# rekuperator_THT.net
KiCad netlist of a schematic drawn in EAGLE
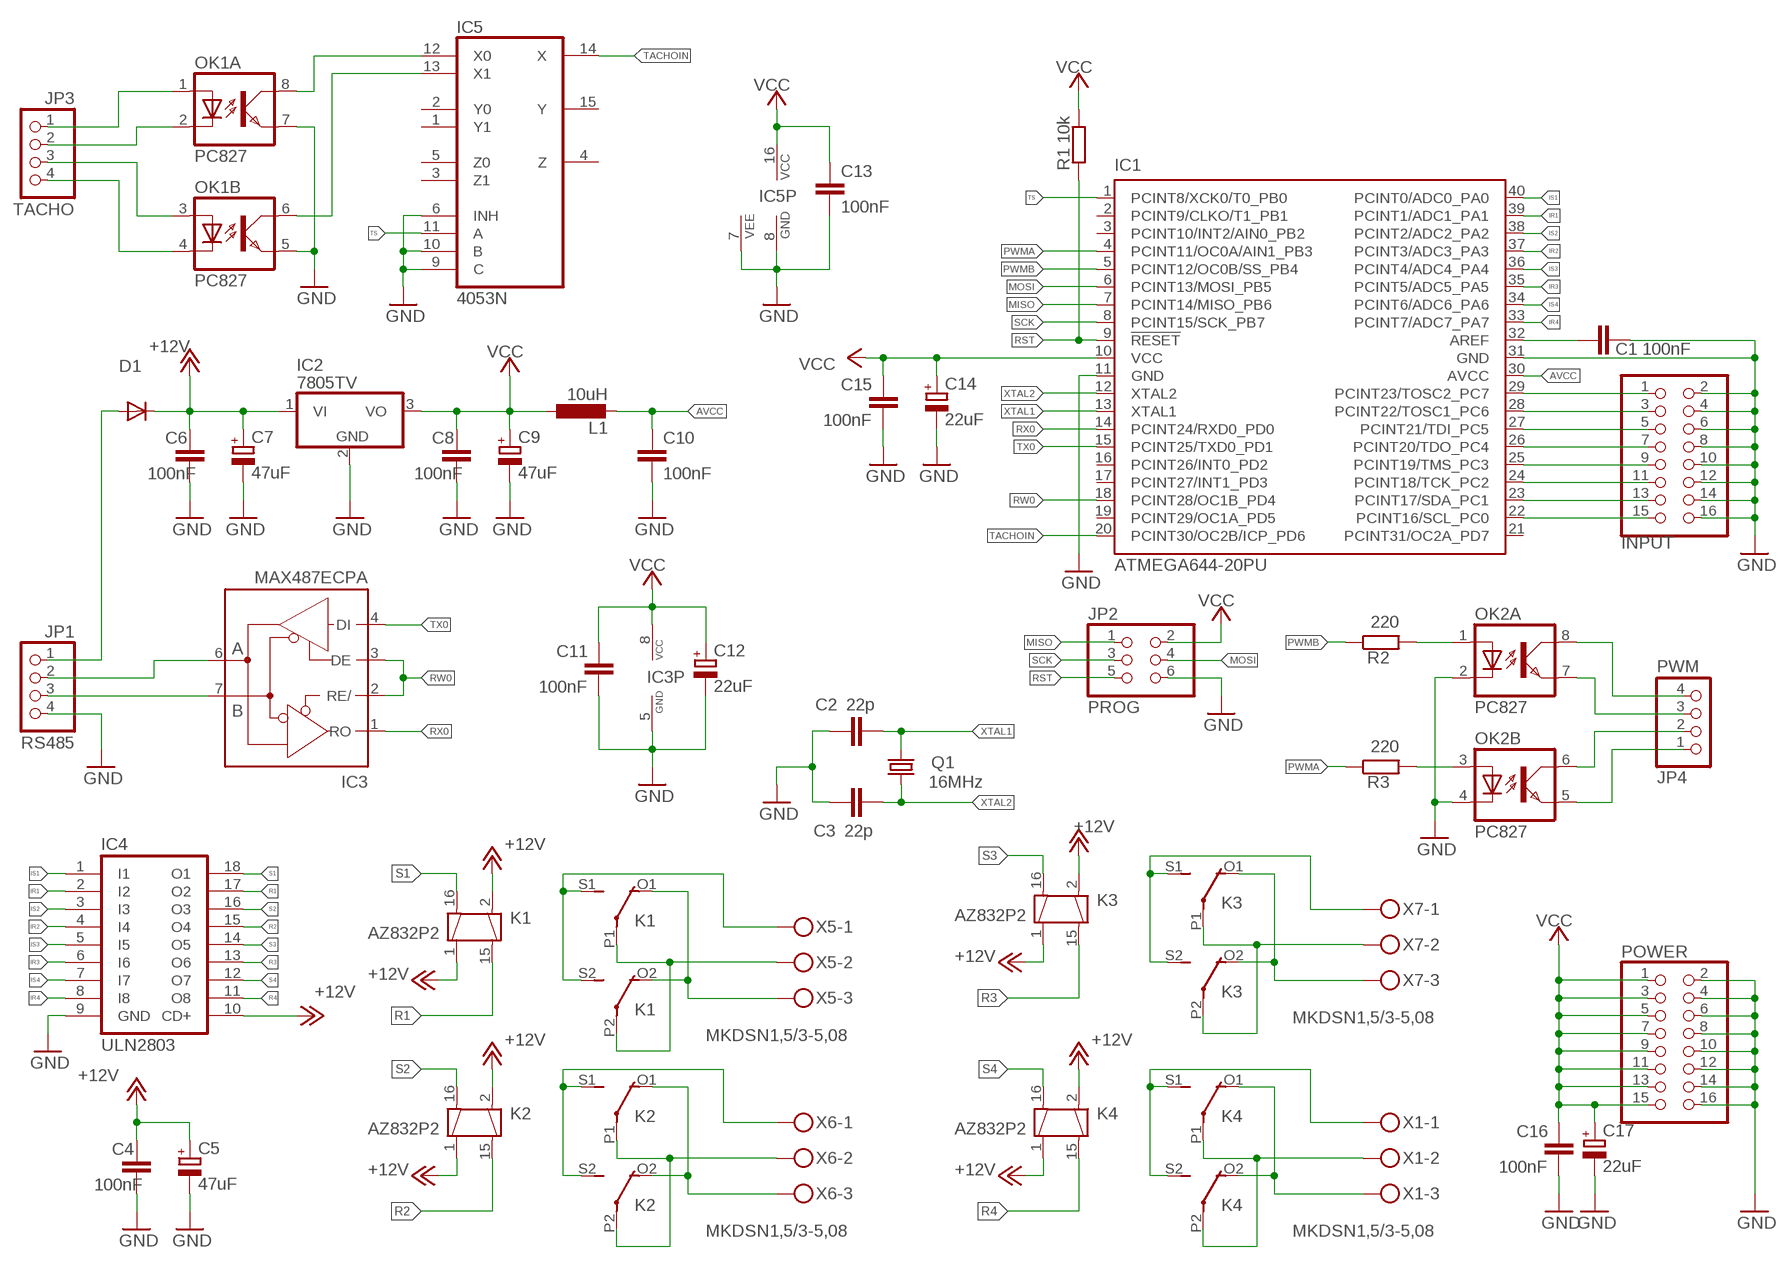
[diagram p0: schematic, sheet 1]

(export (version "E")
  (design (tool "Eeschema 10.0.6"))
  (components
    (comp (ref "C1")
      (value "100nF")
      (footprint "eagle-import:C025-025X050")
      (libsource (lib "eagle-import") (part "C-EU025-025X050"))
    )
    (comp (ref "C2")
      (value "22p")
      (footprint "eagle-import:C025-024X044")
      (libsource (lib "eagle-import") (part "C-EU025-024X044"))
    )
    (comp (ref "C3")
      (value "22p")
      (footprint "eagle-import:C025-024X044")
      (libsource (lib "eagle-import") (part "C-EU025-024X044"))
    )
    (comp (ref "C4")
      (value "100nF")
      (footprint "eagle-import:C025-025X050")
      (libsource (lib "eagle-import") (part "C-EU025-025X050"))
    )
    (comp (ref "C5")
      (value "47uF")
      (footprint "eagle-import:E2,5-6")
      (libsource (lib "eagle-import") (part "CPOL-EUE2.5-6"))
    )
    (comp (ref "C6")
      (value "100nF")
      (footprint "eagle-import:C025-025X050")
      (libsource (lib "eagle-import") (part "C-EU025-025X050"))
    )
    (comp (ref "C7")
      (value "47uF")
      (footprint "eagle-import:E2,5-6")
      (libsource (lib "eagle-import") (part "CPOL-EUE2.5-6"))
    )
    (comp (ref "C8")
      (value "100nF")
      (footprint "eagle-import:C025-025X050")
      (libsource (lib "eagle-import") (part "C-EU025-025X050"))
    )
    (comp (ref "C9")
      (value "47uF")
      (footprint "eagle-import:E2,5-6")
      (libsource (lib "eagle-import") (part "CPOL-EUE2.5-6"))
    )
    (comp (ref "C10")
      (value "100nF")
      (footprint "eagle-import:C025-025X050")
      (libsource (lib "eagle-import") (part "C-EU025-025X050"))
    )
    (comp (ref "C11")
      (value "100nF")
      (footprint "eagle-import:C025-025X050")
      (libsource (lib "eagle-import") (part "C-EU025-025X050"))
    )
    (comp (ref "C12")
      (value "22uF")
      (footprint "eagle-import:E2-5")
      (libsource (lib "eagle-import") (part "CPOL-EUE2-5"))
    )
    (comp (ref "C13")
      (value "100nF")
      (footprint "eagle-import:C025-025X050")
      (libsource (lib "eagle-import") (part "C-EU025-025X050"))
    )
    (comp (ref "C14")
      (value "22uF")
      (footprint "eagle-import:E2-5")
      (libsource (lib "eagle-import") (part "CPOL-EUE2-5"))
    )
    (comp (ref "C15")
      (value "100nF")
      (footprint "eagle-import:C025-025X050")
      (libsource (lib "eagle-import") (part "C-EU025-025X050"))
    )
    (comp (ref "C16")
      (value "100nF")
      (footprint "eagle-import:C025-025X050")
      (libsource (lib "eagle-import") (part "C-EU025-025X050"))
    )
    (comp (ref "C17")
      (value "22uF")
      (footprint "eagle-import:E2-5")
      (libsource (lib "eagle-import") (part "CPOL-EUE2-5"))
    )
    (comp (ref "D1")
      (value "1N4002")
      (footprint "eagle-import:DO34-7")
      (libsource (lib "eagle-import") (part "BAS15"))
    )
    (comp (ref "IC1")
      (value "ATMEGA644-20PU")
      (footprint "eagle-import:DIL40")
      (libsource (lib "eagle-import") (part "ATMEGA644-PU20"))
    )
    (comp (ref "IC2")
      (value "7805TV")
      (footprint "eagle-import:TO220V")
      (libsource (lib "eagle-import") (part "78TV05"))
    )
    (comp (ref "IC3")
      (value "MAX487ECPA")
      (footprint "eagle-import:DIL08")
      (fields (field (name "MPN") "MAX481CPA+"))
      (libsource (lib "eagle-import") (part "MAX481CPA"))
    )
    (comp (ref "IC4")
      (value "ULN2803")
      (footprint "eagle-import:DIL18")
      (libsource (lib "eagle-import") (part "ULN2803A"))
    )
    (comp (ref "IC5")
      (value "4053N")
      (footprint "eagle-import:DIL16")
      (libsource (lib "eagle-import") (part "4053N"))
    )
    (comp (ref "INPUT")
      (value "PINHD-2X8")
      (footprint "eagle-import:2X08")
      (libsource (lib "eagle-import") (part "PINHD-2X8"))
    )
    (comp (ref "JP1")
      (value "RS485")
      (footprint "eagle-import:1X04")
      (libsource (lib "eagle-import") (part "PINHD-1X4"))
    )
    (comp (ref "JP2")
      (value "PROG")
      (footprint "eagle-import:2X03")
      (libsource (lib "eagle-import") (part "PINHD-2X3"))
    )
    (comp (ref "JP3")
      (value "TACHO")
      (footprint "eagle-import:1X04")
      (libsource (lib "eagle-import") (part "PINHD-1X4"))
    )
    (comp (ref "JP4")
      (value "PWM")
      (footprint "eagle-import:1X04")
      (libsource (lib "eagle-import") (part "PINHD-1X4"))
    )
    (comp (ref "K1")
      (value "AZ832P2")
      (footprint "eagle-import:DS2E-L2")
      (libsource (lib "eagle-import") (part "DS2-L2-24V"))
    )
    (comp (ref "K2")
      (value "AZ832P2")
      (footprint "eagle-import:DS2E-L2")
      (libsource (lib "eagle-import") (part "DS2-L2-24V"))
    )
    (comp (ref "K3")
      (value "AZ832P2")
      (footprint "eagle-import:DS2E-L2")
      (libsource (lib "eagle-import") (part "DS2-L2-24V"))
    )
    (comp (ref "K4")
      (value "AZ832P2")
      (footprint "eagle-import:DS2E-L2")
      (libsource (lib "eagle-import") (part "DS2-L2-24V"))
    )
    (comp (ref "L1")
      (value "10uH")
      (footprint "eagle-import:0207_12")
      (libsource (lib "eagle-import") (part "L-EU0207/12"))
    )
    (comp (ref "OK1")
      (value "PC827")
      (footprint "eagle-import:DIL08")
      (libsource (lib "eagle-import") (part "PC827"))
    )
    (comp (ref "OK2")
      (value "PC827")
      (footprint "eagle-import:DIL08")
      (libsource (lib "eagle-import") (part "PC827"))
    )
    (comp (ref "POWER")
      (value "PINHD-2X8")
      (footprint "eagle-import:2X08")
      (libsource (lib "eagle-import") (part "PINHD-2X8"))
    )
    (comp (ref "Q1")
      (value "16MHz")
      (footprint "eagle-import:HC49_S")
      (libsource (lib "eagle-import") (part "CRYSTALHC49S"))
    )
    (comp (ref "R1")
      (value "10k")
      (footprint "eagle-import:0204V")
      (libsource (lib "eagle-import") (part "R-EU_0204/2V"))
    )
    (comp (ref "R2")
      (value "220")
      (footprint "eagle-import:0207_12")
      (libsource (lib "eagle-import") (part "R-EU_0207/12"))
    )
    (comp (ref "R3")
      (value "220")
      (footprint "eagle-import:0207_12")
      (libsource (lib "eagle-import") (part "R-EU_0207/12"))
    )
    (comp (ref "X1")
      (value "MKDSN1,5/3-5,08")
      (footprint "eagle-import:MKDSN1,5_3-5,08")
      (fields (field (name "MPN") "SMKDSN1,5/3-5,08"))
      (libsource (lib "eagle-import") (part "MKDSN1,5/3-5,08"))
    )
    (comp (ref "X5")
      (value "MKDSN1,5/3-5,08")
      (footprint "eagle-import:MKDSN1,5_3-5,08")
      (fields (field (name "MPN") "SMKDSN1,5/3-5,08"))
      (libsource (lib "eagle-import") (part "MKDSN1,5/3-5,08"))
    )
    (comp (ref "X6")
      (value "MKDSN1,5/3-5,08")
      (footprint "eagle-import:MKDSN1,5_3-5,08")
      (fields (field (name "MPN") "SMKDSN1,5/3-5,08"))
      (libsource (lib "eagle-import") (part "MKDSN1,5/3-5,08"))
    )
    (comp (ref "X7")
      (value "MKDSN1,5/3-5,08")
      (footprint "eagle-import:MKDSN1,5_3-5,08")
      (fields (field (name "MPN") "SMKDSN1,5/3-5,08"))
      (libsource (lib "eagle-import") (part "MKDSN1,5/3-5,08"))
    )
  )
  (nets
    (net (code "1") (name "+12V") (class "Default")
      (node (ref "C4") (pin "1") (pinfunction "1_1") (pintype "passive"))
      (node (ref "C5") (pin "+") (pinfunction "+_+") (pintype "passive"))
      (node (ref "C6") (pin "1") (pinfunction "1_1") (pintype "passive"))
      (node (ref "C7") (pin "+") (pinfunction "+_+") (pintype "passive"))
      (node (ref "D1") (pin "C") (pinfunction "C_C") (pintype "passive"))
      (node (ref "IC2") (pin "1") (pinfunction "VI_1") (pintype "input"))
      (node (ref "IC4") (pin "10") (pinfunction "CD+_10") (pintype "passive"))
      (node (ref "K1") (pin "1") (pinfunction "2_1") (pintype "passive"))
      (node (ref "K1") (pin "2") (pinfunction "3_2") (pintype "passive"))
      (node (ref "K2") (pin "1") (pinfunction "2_1") (pintype "passive"))
      (node (ref "K2") (pin "2") (pinfunction "3_2") (pintype "passive"))
      (node (ref "K3") (pin "1") (pinfunction "2_1") (pintype "passive"))
      (node (ref "K3") (pin "2") (pinfunction "3_2") (pintype "passive"))
      (node (ref "K4") (pin "1") (pinfunction "2_1") (pintype "passive"))
      (node (ref "K4") (pin "2") (pinfunction "3_2") (pintype "passive"))
    )
    (net (code "2") (name "AVCC") (class "Default")
      (node (ref "C10") (pin "1") (pinfunction "1_1") (pintype "passive"))
      (node (ref "IC1") (pin "30") (pinfunction "AVCC_30") (pintype "power_in"))
      (node (ref "L1") (pin "2") (pinfunction "2_2") (pintype "passive"))
    )
    (net (code "3") (name "GND") (class "Default")
      (node (ref "C1") (pin "2") (pinfunction "2_2") (pintype "passive"))
      (node (ref "C10") (pin "2") (pinfunction "2_2") (pintype "passive"))
      (node (ref "C11") (pin "2") (pinfunction "2_2") (pintype "passive"))
      (node (ref "C12") (pin "-") (pinfunction "-_-") (pintype "passive"))
      (node (ref "C13") (pin "2") (pinfunction "2_2") (pintype "passive"))
      (node (ref "C14") (pin "-") (pinfunction "-_-") (pintype "passive"))
      (node (ref "C15") (pin "2") (pinfunction "2_2") (pintype "passive"))
      (node (ref "C16") (pin "2") (pinfunction "2_2") (pintype "passive"))
      (node (ref "C17") (pin "-") (pinfunction "-_-") (pintype "passive"))
      (node (ref "C2") (pin "1") (pinfunction "1_1") (pintype "passive"))
      (node (ref "C3") (pin "1") (pinfunction "1_1") (pintype "passive"))
      (node (ref "C4") (pin "2") (pinfunction "2_2") (pintype "passive"))
      (node (ref "C5") (pin "-") (pinfunction "-_-") (pintype "passive"))
      (node (ref "C6") (pin "2") (pinfunction "2_2") (pintype "passive"))
      (node (ref "C7") (pin "-") (pinfunction "-_-") (pintype "passive"))
      (node (ref "C8") (pin "2") (pinfunction "2_2") (pintype "passive"))
      (node (ref "C9") (pin "-") (pinfunction "-_-") (pintype "passive"))
      (node (ref "IC1") (pin "11") (pinfunction "GND_11") (pintype "power_in"))
      (node (ref "IC1") (pin "31") (pinfunction "GND_31") (pintype "power_in"))
      (node (ref "IC2") (pin "2") (pinfunction "GND_2") (pintype "passive"))
      (node (ref "IC3") (pin "5") (pinfunction "GND_5") (pintype "power_in"))
      (node (ref "IC4") (pin "9") (pinfunction "GND_9") (pintype "power_in"))
      (node (ref "IC5") (pin "10") (pinfunction "B_10") (pintype "input"))
      (node (ref "IC5") (pin "6") (pinfunction "INH_6") (pintype "input"))
      (node (ref "IC5") (pin "7") (pinfunction "VEE_7") (pintype "power_in"))
      (node (ref "IC5") (pin "8") (pinfunction "GND_8") (pintype "power_in"))
      (node (ref "IC5") (pin "9") (pinfunction "C_9") (pintype "input"))
      (node (ref "INPUT") (pin "10") (pinfunction "10_10") (pintype "passive"))
      (node (ref "INPUT") (pin "12") (pinfunction "12_12") (pintype "passive"))
      (node (ref "INPUT") (pin "14") (pinfunction "14_14") (pintype "passive"))
      (node (ref "INPUT") (pin "16") (pinfunction "16_16") (pintype "passive"))
      (node (ref "INPUT") (pin "2") (pinfunction "2_2") (pintype "passive"))
      (node (ref "INPUT") (pin "4") (pinfunction "4_4") (pintype "passive"))
      (node (ref "INPUT") (pin "6") (pinfunction "6_6") (pintype "passive"))
      (node (ref "INPUT") (pin "8") (pinfunction "8_8") (pintype "passive"))
      (node (ref "JP1") (pin "4") (pinfunction "4_4") (pintype "passive"))
      (node (ref "JP2") (pin "6") (pinfunction "6_6") (pintype "passive"))
      (node (ref "OK1") (pin "5") (pinfunction "EMIT_5") (pintype "passive"))
      (node (ref "OK1") (pin "7") (pinfunction "EMIT_7") (pintype "passive"))
      (node (ref "OK2") (pin "2") (pinfunction "C_2") (pintype "passive"))
      (node (ref "OK2") (pin "4") (pinfunction "C_4") (pintype "passive"))
      (node (ref "POWER") (pin "10") (pinfunction "10_10") (pintype "passive"))
      (node (ref "POWER") (pin "12") (pinfunction "12_12") (pintype "passive"))
      (node (ref "POWER") (pin "14") (pinfunction "14_14") (pintype "passive"))
      (node (ref "POWER") (pin "16") (pinfunction "16_16") (pintype "passive"))
      (node (ref "POWER") (pin "2") (pinfunction "2_2") (pintype "passive"))
      (node (ref "POWER") (pin "4") (pinfunction "4_4") (pintype "passive"))
      (node (ref "POWER") (pin "6") (pinfunction "6_6") (pintype "passive"))
      (node (ref "POWER") (pin "8") (pinfunction "8_8") (pintype "passive"))
    )
    (net (code "4") (name "IR1") (class "Default")
      (node (ref "IC1") (pin "39") (pinfunction "PCINT1/ADC1_PA1_39") (pintype "bidirectional"))
      (node (ref "IC4") (pin "2") (pinfunction "I2_2") (pintype "input"))
    )
    (net (code "5") (name "IR2") (class "Default")
      (node (ref "IC1") (pin "37") (pinfunction "PCINT3/ADC3_PA3_37") (pintype "bidirectional"))
      (node (ref "IC4") (pin "4") (pinfunction "I4_4") (pintype "input"))
    )
    (net (code "6") (name "IR3") (class "Default")
      (node (ref "IC1") (pin "35") (pinfunction "PCINT5/ADC5_PA5_35") (pintype "bidirectional"))
      (node (ref "IC4") (pin "6") (pinfunction "I6_6") (pintype "input"))
    )
    (net (code "7") (name "IR4") (class "Default")
      (node (ref "IC1") (pin "33") (pinfunction "PCINT7/ADC7_PA7_33") (pintype "bidirectional"))
      (node (ref "IC4") (pin "8") (pinfunction "I8_8") (pintype "input"))
    )
    (net (code "8") (name "IS1") (class "Default")
      (node (ref "IC1") (pin "40") (pinfunction "PCINT0/ADC0_PA0_40") (pintype "bidirectional"))
      (node (ref "IC4") (pin "1") (pinfunction "I1_1") (pintype "input"))
    )
    (net (code "9") (name "IS2") (class "Default")
      (node (ref "IC1") (pin "38") (pinfunction "PCINT2/ADC2_PA2_38") (pintype "bidirectional"))
      (node (ref "IC4") (pin "3") (pinfunction "I3_3") (pintype "input"))
    )
    (net (code "10") (name "IS3") (class "Default")
      (node (ref "IC1") (pin "36") (pinfunction "PCINT4/ADC4_PA4_36") (pintype "bidirectional"))
      (node (ref "IC4") (pin "5") (pinfunction "I5_5") (pintype "input"))
    )
    (net (code "11") (name "IS4") (class "Default")
      (node (ref "IC1") (pin "34") (pinfunction "PCINT6/ADC6_PA6_34") (pintype "bidirectional"))
      (node (ref "IC4") (pin "7") (pinfunction "I7_7") (pintype "input"))
    )
    (net (code "12") (name "MISO") (class "Default")
      (node (ref "IC1") (pin "7") (pinfunction "PCINT14/MISO_PB6_7") (pintype "bidirectional"))
      (node (ref "JP2") (pin "1") (pinfunction "1_1") (pintype "passive"))
    )
    (net (code "13") (name "MOSI") (class "Default")
      (node (ref "IC1") (pin "6") (pinfunction "PCINT13/MOSI_PB5_6") (pintype "bidirectional"))
      (node (ref "JP2") (pin "4") (pinfunction "4_4") (pintype "passive"))
    )
    (net (code "14") (name "Net-(D1-PadA)") (class "Default")
      (node (ref "D1") (pin "A") (pinfunction "A_A") (pintype "passive"))
      (node (ref "JP1") (pin "1") (pinfunction "1_1") (pintype "passive"))
    )
    (net (code "15") (name "Net-(IC1-AREF)") (class "Default")
      (node (ref "C1") (pin "1") (pinfunction "1_1") (pintype "passive"))
      (node (ref "IC1") (pin "32") (pinfunction "AREF_32") (pintype "passive"))
    )
    (net (code "16") (name "Net-(IC1-PCINT16{slash}SCL_PC0)") (class "Default")
      (node (ref "IC1") (pin "22") (pinfunction "PCINT16/SCL_PC0_22") (pintype "bidirectional"))
      (node (ref "INPUT") (pin "15") (pinfunction "15_15") (pintype "passive"))
    )
    (net (code "17") (name "Net-(IC1-PCINT17{slash}SDA_PC1)") (class "Default")
      (node (ref "IC1") (pin "23") (pinfunction "PCINT17/SDA_PC1_23") (pintype "bidirectional"))
      (node (ref "INPUT") (pin "13") (pinfunction "13_13") (pintype "passive"))
    )
    (net (code "18") (name "Net-(IC1-PCINT18{slash}TCK_PC2)") (class "Default")
      (node (ref "IC1") (pin "24") (pinfunction "PCINT18/TCK_PC2_24") (pintype "bidirectional"))
      (node (ref "INPUT") (pin "11") (pinfunction "11_11") (pintype "passive"))
    )
    (net (code "19") (name "Net-(IC1-PCINT19{slash}TMS_PC3)") (class "Default")
      (node (ref "IC1") (pin "25") (pinfunction "PCINT19/TMS_PC3_25") (pintype "bidirectional"))
      (node (ref "INPUT") (pin "9") (pinfunction "9_9") (pintype "passive"))
    )
    (net (code "20") (name "Net-(IC1-PCINT20{slash}TDO_PC4)") (class "Default")
      (node (ref "IC1") (pin "26") (pinfunction "PCINT20/TDO_PC4_26") (pintype "bidirectional"))
      (node (ref "INPUT") (pin "7") (pinfunction "7_7") (pintype "passive"))
    )
    (net (code "21") (name "Net-(IC1-PCINT21{slash}TDI_PC5)") (class "Default")
      (node (ref "IC1") (pin "27") (pinfunction "PCINT21/TDI_PC5_27") (pintype "bidirectional"))
      (node (ref "INPUT") (pin "5") (pinfunction "5_5") (pintype "passive"))
    )
    (net (code "22") (name "Net-(IC1-PCINT22{slash}TOSC1_PC6)") (class "Default")
      (node (ref "IC1") (pin "28") (pinfunction "PCINT22/TOSC1_PC6_28") (pintype "bidirectional"))
      (node (ref "INPUT") (pin "3") (pinfunction "3_3") (pintype "passive"))
    )
    (net (code "23") (name "Net-(IC1-PCINT23{slash}TOSC2_PC7)") (class "Default")
      (node (ref "IC1") (pin "29") (pinfunction "PCINT23/TOSC2_PC7_29") (pintype "bidirectional"))
      (node (ref "INPUT") (pin "1") (pinfunction "1_1") (pintype "passive"))
    )
    (net (code "24") (name "Net-(IC3A-A)") (class "Default")
      (node (ref "IC3") (pin "6") (pinfunction "A_6") (pintype "passive"))
      (node (ref "JP1") (pin "2") (pinfunction "2_2") (pintype "passive"))
    )
    (net (code "25") (name "Net-(IC3A-B)") (class "Default")
      (node (ref "IC3") (pin "7") (pinfunction "B_7") (pintype "passive"))
      (node (ref "JP1") (pin "3") (pinfunction "3_3") (pintype "passive"))
    )
    (net (code "26") (name "Net-(IC5A-X0)") (class "Default")
      (node (ref "IC5") (pin "12") (pinfunction "X0_12") (pintype "bidirectional"))
      (node (ref "OK1") (pin "8") (pinfunction "COL_8") (pintype "passive"))
    )
    (net (code "27") (name "Net-(IC5A-X1)") (class "Default")
      (node (ref "IC5") (pin "13") (pinfunction "X1_13") (pintype "bidirectional"))
      (node (ref "OK1") (pin "6") (pinfunction "COL_6") (pintype "passive"))
    )
    (net (code "28") (name "Net-(K1B-O)") (class "Default")
      (node (ref "K1") (pin "O1") (pinfunction "O_O1") (pintype "passive"))
      (node (ref "K1") (pin "O2") (pinfunction "O_O2") (pintype "passive"))
      (node (ref "X5") (pin "3") (pinfunction "KL_3") (pintype "passive"))
    )
    (net (code "29") (name "Net-(K1B-P)") (class "Default")
      (node (ref "K1") (pin "P1") (pinfunction "P_P1") (pintype "passive"))
      (node (ref "K1") (pin "P2") (pinfunction "P_P2") (pintype "passive"))
      (node (ref "X5") (pin "2") (pinfunction "KL_2") (pintype "passive"))
    )
    (net (code "30") (name "Net-(K1B-S)") (class "Default")
      (node (ref "K1") (pin "S1") (pinfunction "S_S1") (pintype "passive"))
      (node (ref "K1") (pin "S2") (pinfunction "S_S2") (pintype "passive"))
      (node (ref "X5") (pin "1") (pinfunction "KL_1") (pintype "passive"))
    )
    (net (code "31") (name "Net-(K2B-O)") (class "Default")
      (node (ref "K2") (pin "O1") (pinfunction "O_O1") (pintype "passive"))
      (node (ref "K2") (pin "O2") (pinfunction "O_O2") (pintype "passive"))
      (node (ref "X6") (pin "3") (pinfunction "KL_3") (pintype "passive"))
    )
    (net (code "32") (name "Net-(K2B-P)") (class "Default")
      (node (ref "K2") (pin "P1") (pinfunction "P_P1") (pintype "passive"))
      (node (ref "K2") (pin "P2") (pinfunction "P_P2") (pintype "passive"))
      (node (ref "X6") (pin "2") (pinfunction "KL_2") (pintype "passive"))
    )
    (net (code "33") (name "Net-(K2B-S)") (class "Default")
      (node (ref "K2") (pin "S1") (pinfunction "S_S1") (pintype "passive"))
      (node (ref "K2") (pin "S2") (pinfunction "S_S2") (pintype "passive"))
      (node (ref "X6") (pin "1") (pinfunction "KL_1") (pintype "passive"))
    )
    (net (code "34") (name "Net-(K3B-O)") (class "Default")
      (node (ref "K3") (pin "O1") (pinfunction "O_O1") (pintype "passive"))
      (node (ref "K3") (pin "O2") (pinfunction "O_O2") (pintype "passive"))
      (node (ref "X7") (pin "3") (pinfunction "KL_3") (pintype "passive"))
    )
    (net (code "35") (name "Net-(K3B-P)") (class "Default")
      (node (ref "K3") (pin "P1") (pinfunction "P_P1") (pintype "passive"))
      (node (ref "K3") (pin "P2") (pinfunction "P_P2") (pintype "passive"))
      (node (ref "X7") (pin "2") (pinfunction "KL_2") (pintype "passive"))
    )
    (net (code "36") (name "Net-(K3B-S)") (class "Default")
      (node (ref "K3") (pin "S1") (pinfunction "S_S1") (pintype "passive"))
      (node (ref "K3") (pin "S2") (pinfunction "S_S2") (pintype "passive"))
      (node (ref "X7") (pin "1") (pinfunction "KL_1") (pintype "passive"))
    )
    (net (code "37") (name "Net-(K4B-O)") (class "Default")
      (node (ref "K4") (pin "O1") (pinfunction "O_O1") (pintype "passive"))
      (node (ref "K4") (pin "O2") (pinfunction "O_O2") (pintype "passive"))
      (node (ref "X1") (pin "3") (pinfunction "KL_3") (pintype "passive"))
    )
    (net (code "38") (name "Net-(K4B-P)") (class "Default")
      (node (ref "K4") (pin "P1") (pinfunction "P_P1") (pintype "passive"))
      (node (ref "K4") (pin "P2") (pinfunction "P_P2") (pintype "passive"))
      (node (ref "X1") (pin "2") (pinfunction "KL_2") (pintype "passive"))
    )
    (net (code "39") (name "Net-(K4B-S)") (class "Default")
      (node (ref "K4") (pin "S1") (pinfunction "S_S1") (pintype "passive"))
      (node (ref "K4") (pin "S2") (pinfunction "S_S2") (pintype "passive"))
      (node (ref "X1") (pin "1") (pinfunction "KL_1") (pintype "passive"))
    )
    (net (code "40") (name "Net-(OK1A-A)") (class "Default")
      (node (ref "JP3") (pin "1") (pinfunction "1_1") (pintype "passive"))
      (node (ref "OK1") (pin "1") (pinfunction "A_1") (pintype "passive"))
    )
    (net (code "41") (name "Net-(OK1A-C)") (class "Default")
      (node (ref "JP3") (pin "2") (pinfunction "2_2") (pintype "passive"))
      (node (ref "OK1") (pin "2") (pinfunction "C_2") (pintype "passive"))
    )
    (net (code "42") (name "Net-(OK1B-A)") (class "Default")
      (node (ref "JP3") (pin "3") (pinfunction "3_3") (pintype "passive"))
      (node (ref "OK1") (pin "3") (pinfunction "A_3") (pintype "passive"))
    )
    (net (code "43") (name "Net-(OK1B-C)") (class "Default")
      (node (ref "JP3") (pin "4") (pinfunction "4_4") (pintype "passive"))
      (node (ref "OK1") (pin "4") (pinfunction "C_4") (pintype "passive"))
    )
    (net (code "44") (name "Net-(OK2A-A)") (class "Default")
      (node (ref "OK2") (pin "1") (pinfunction "A_1") (pintype "passive"))
      (node (ref "R2") (pin "2") (pinfunction "2_2") (pintype "passive"))
    )
    (net (code "45") (name "Net-(OK2A-COL)") (class "Default")
      (node (ref "JP4") (pin "4") (pinfunction "4_4") (pintype "passive"))
      (node (ref "OK2") (pin "8") (pinfunction "COL_8") (pintype "passive"))
    )
    (net (code "46") (name "Net-(OK2A-EMIT)") (class "Default")
      (node (ref "JP4") (pin "3") (pinfunction "3_3") (pintype "passive"))
      (node (ref "OK2") (pin "7") (pinfunction "EMIT_7") (pintype "passive"))
    )
    (net (code "47") (name "Net-(OK2B-A)") (class "Default")
      (node (ref "OK2") (pin "3") (pinfunction "A_3") (pintype "passive"))
      (node (ref "R3") (pin "2") (pinfunction "2_2") (pintype "passive"))
    )
    (net (code "48") (name "Net-(OK2B-COL)") (class "Default")
      (node (ref "JP4") (pin "2") (pinfunction "2_2") (pintype "passive"))
      (node (ref "OK2") (pin "6") (pinfunction "COL_6") (pintype "passive"))
    )
    (net (code "49") (name "Net-(OK2B-EMIT)") (class "Default")
      (node (ref "JP4") (pin "1") (pinfunction "1_1") (pintype "passive"))
      (node (ref "OK2") (pin "5") (pinfunction "EMIT_5") (pintype "passive"))
    )
    (net (code "50") (name "PWMA") (class "Default")
      (node (ref "IC1") (pin "4") (pinfunction "PCINT11/OC0A/AIN1_PB3_4") (pintype "bidirectional"))
      (node (ref "R3") (pin "1") (pinfunction "1_1") (pintype "passive"))
    )
    (net (code "51") (name "PWMB") (class "Default")
      (node (ref "IC1") (pin "5") (pinfunction "PCINT12/OC0B/SS_PB4_5") (pintype "bidirectional"))
      (node (ref "R2") (pin "1") (pinfunction "1_1") (pintype "passive"))
    )
    (net (code "52") (name "R1") (class "Default")
      (node (ref "IC4") (pin "17") (pinfunction "O2_17") (pintype "open_collector"))
      (node (ref "K1") (pin "15") (pinfunction "4_15") (pintype "passive"))
    )
    (net (code "53") (name "R2") (class "Default")
      (node (ref "IC4") (pin "15") (pinfunction "O4_15") (pintype "open_collector"))
      (node (ref "K2") (pin "15") (pinfunction "4_15") (pintype "passive"))
    )
    (net (code "54") (name "R3") (class "Default")
      (node (ref "IC4") (pin "13") (pinfunction "O6_13") (pintype "open_collector"))
      (node (ref "K3") (pin "15") (pinfunction "4_15") (pintype "passive"))
    )
    (net (code "55") (name "R4") (class "Default")
      (node (ref "IC4") (pin "11") (pinfunction "O8_11") (pintype "open_collector"))
      (node (ref "K4") (pin "15") (pinfunction "4_15") (pintype "passive"))
    )
    (net (code "56") (name "RST") (class "Default")
      (node (ref "IC1") (pin "9") (pinfunction "~{RESET}_9") (pintype "input"))
      (node (ref "JP2") (pin "5") (pinfunction "5_5") (pintype "passive"))
      (node (ref "R1") (pin "2") (pinfunction "2_2") (pintype "passive"))
    )
    (net (code "57") (name "RW0") (class "Default")
      (node (ref "IC1") (pin "18") (pinfunction "PCINT28/OC1B_PD4_18") (pintype "bidirectional"))
      (node (ref "IC3") (pin "2") (pinfunction "RE/_2") (pintype "input"))
      (node (ref "IC3") (pin "3") (pinfunction "DE_3") (pintype "input"))
    )
    (net (code "58") (name "RX0") (class "Default")
      (node (ref "IC1") (pin "14") (pinfunction "PCINT24/RXD0_PD0_14") (pintype "bidirectional"))
      (node (ref "IC3") (pin "1") (pinfunction "RO_1") (pintype "output"))
    )
    (net (code "59") (name "S1") (class "Default")
      (node (ref "IC4") (pin "18") (pinfunction "O1_18") (pintype "open_collector"))
      (node (ref "K1") (pin "16") (pinfunction "1_16") (pintype "passive"))
    )
    (net (code "60") (name "S2") (class "Default")
      (node (ref "IC4") (pin "16") (pinfunction "O3_16") (pintype "open_collector"))
      (node (ref "K2") (pin "16") (pinfunction "1_16") (pintype "passive"))
    )
    (net (code "61") (name "S3") (class "Default")
      (node (ref "IC4") (pin "14") (pinfunction "O5_14") (pintype "open_collector"))
      (node (ref "K3") (pin "16") (pinfunction "1_16") (pintype "passive"))
    )
    (net (code "62") (name "S4") (class "Default")
      (node (ref "IC4") (pin "12") (pinfunction "O7_12") (pintype "open_collector"))
      (node (ref "K4") (pin "16") (pinfunction "1_16") (pintype "passive"))
    )
    (net (code "63") (name "SCK") (class "Default")
      (node (ref "IC1") (pin "8") (pinfunction "PCINT15/SCK_PB7_8") (pintype "bidirectional"))
      (node (ref "JP2") (pin "3") (pinfunction "3_3") (pintype "passive"))
    )
    (net (code "64") (name "TACHOIN") (class "Default")
      (node (ref "IC1") (pin "20") (pinfunction "PCINT30/OC2B/ICP_PD6_20") (pintype "bidirectional"))
      (node (ref "IC5") (pin "14") (pinfunction "X_14") (pintype "bidirectional"))
    )
    (net (code "65") (name "TS") (class "Default")
      (node (ref "IC1") (pin "1") (pinfunction "PCINT8/XCK0/T0_PB0_1") (pintype "bidirectional"))
      (node (ref "IC5") (pin "11") (pinfunction "A_11") (pintype "input"))
    )
    (net (code "66") (name "TX0") (class "Default")
      (node (ref "IC1") (pin "15") (pinfunction "PCINT25/TXD0_PD1_15") (pintype "bidirectional"))
      (node (ref "IC3") (pin "4") (pinfunction "DI_4") (pintype "input"))
    )
    (net (code "67") (name "VCC") (class "Default")
      (node (ref "C11") (pin "1") (pinfunction "1_1") (pintype "passive"))
      (node (ref "C12") (pin "+") (pinfunction "+_+") (pintype "passive"))
      (node (ref "C13") (pin "1") (pinfunction "1_1") (pintype "passive"))
      (node (ref "C14") (pin "+") (pinfunction "+_+") (pintype "passive"))
      (node (ref "C15") (pin "1") (pinfunction "1_1") (pintype "passive"))
      (node (ref "C16") (pin "1") (pinfunction "1_1") (pintype "passive"))
      (node (ref "C17") (pin "+") (pinfunction "+_+") (pintype "passive"))
      (node (ref "C8") (pin "1") (pinfunction "1_1") (pintype "passive"))
      (node (ref "C9") (pin "+") (pinfunction "+_+") (pintype "passive"))
      (node (ref "IC1") (pin "10") (pinfunction "VCC_10") (pintype "power_in"))
      (node (ref "IC2") (pin "3") (pinfunction "VO_3") (pintype "passive"))
      (node (ref "IC3") (pin "8") (pinfunction "VCC_8") (pintype "power_in"))
      (node (ref "IC5") (pin "16") (pinfunction "VCC_16") (pintype "power_in"))
      (node (ref "JP2") (pin "2") (pinfunction "2_2") (pintype "passive"))
      (node (ref "L1") (pin "1") (pinfunction "1_1") (pintype "passive"))
      (node (ref "POWER") (pin "1") (pinfunction "1_1") (pintype "passive"))
      (node (ref "POWER") (pin "11") (pinfunction "11_11") (pintype "passive"))
      (node (ref "POWER") (pin "13") (pinfunction "13_13") (pintype "passive"))
      (node (ref "POWER") (pin "15") (pinfunction "15_15") (pintype "passive"))
      (node (ref "POWER") (pin "3") (pinfunction "3_3") (pintype "passive"))
      (node (ref "POWER") (pin "5") (pinfunction "5_5") (pintype "passive"))
      (node (ref "POWER") (pin "7") (pinfunction "7_7") (pintype "passive"))
      (node (ref "POWER") (pin "9") (pinfunction "9_9") (pintype "passive"))
      (node (ref "R1") (pin "1") (pinfunction "1_1") (pintype "passive"))
    )
    (net (code "68") (name "XTAL1") (class "Default")
      (node (ref "C2") (pin "2") (pinfunction "2_2") (pintype "passive"))
      (node (ref "IC1") (pin "13") (pinfunction "XTAL1_13") (pintype "input"))
      (node (ref "Q1") (pin "2") (pinfunction "2_2") (pintype "passive"))
    )
    (net (code "69") (name "XTAL2") (class "Default")
      (node (ref "C3") (pin "2") (pinfunction "2_2") (pintype "passive"))
      (node (ref "IC1") (pin "12") (pinfunction "XTAL2_12") (pintype "output"))
      (node (ref "Q1") (pin "1") (pinfunction "1_1") (pintype "passive"))
    )
    (net (code "70") (name "unconnected-(IC1-PCINT9{slash}CLKO{slash}T1_PB1-Pad2)") (class "Default")
      (node (ref "IC1") (pin "2") (pinfunction "PCINT9/CLKO/T1_PB1_2") (pintype "bidirectional"))
    )
    (net (code "71") (name "unconnected-(IC1-PCINT10{slash}INT2{slash}AIN0_PB2-Pad3)") (class "Default")
      (node (ref "IC1") (pin "3") (pinfunction "PCINT10/INT2/AIN0_PB2_3") (pintype "bidirectional"))
    )
    (net (code "72") (name "unconnected-(IC1-PCINT26{slash}INT0_PD2-Pad16)") (class "Default")
      (node (ref "IC1") (pin "16") (pinfunction "PCINT26/INT0_PD2_16") (pintype "bidirectional"))
    )
    (net (code "73") (name "unconnected-(IC1-PCINT27{slash}INT1_PD3-Pad17)") (class "Default")
      (node (ref "IC1") (pin "17") (pinfunction "PCINT27/INT1_PD3_17") (pintype "bidirectional"))
    )
    (net (code "74") (name "unconnected-(IC1-PCINT29{slash}OC1A_PD5-Pad19)") (class "Default")
      (node (ref "IC1") (pin "19") (pinfunction "PCINT29/OC1A_PD5_19") (pintype "bidirectional"))
    )
    (net (code "75") (name "unconnected-(IC1-PCINT31{slash}OC2A_PD7-Pad21)") (class "Default")
      (node (ref "IC1") (pin "21") (pinfunction "PCINT31/OC2A_PD7_21") (pintype "bidirectional"))
    )
    (net (code "76") (name "unconnected-(IC5A-Y-Pad15)") (class "Default")
      (node (ref "IC5") (pin "15") (pinfunction "Y_15") (pintype "bidirectional"))
    )
    (net (code "77") (name "unconnected-(IC5A-Y0-Pad2)") (class "Default")
      (node (ref "IC5") (pin "2") (pinfunction "Y0_2") (pintype "bidirectional"))
    )
    (net (code "78") (name "unconnected-(IC5A-Y1-Pad1)") (class "Default")
      (node (ref "IC5") (pin "1") (pinfunction "Y1_1") (pintype "bidirectional"))
    )
    (net (code "79") (name "unconnected-(IC5A-Z-Pad4)") (class "Default")
      (node (ref "IC5") (pin "4") (pinfunction "Z_4") (pintype "bidirectional"))
    )
    (net (code "80") (name "unconnected-(IC5A-Z0-Pad5)") (class "Default")
      (node (ref "IC5") (pin "5") (pinfunction "Z0_5") (pintype "bidirectional"))
    )
    (net (code "81") (name "unconnected-(IC5A-Z1-Pad3)") (class "Default")
      (node (ref "IC5") (pin "3") (pinfunction "Z1_3") (pintype "bidirectional"))
    )
  )
)
